# ESP_Grow_Rev_A.net
KiCad netlist of a schematic drawn in Altium Designer
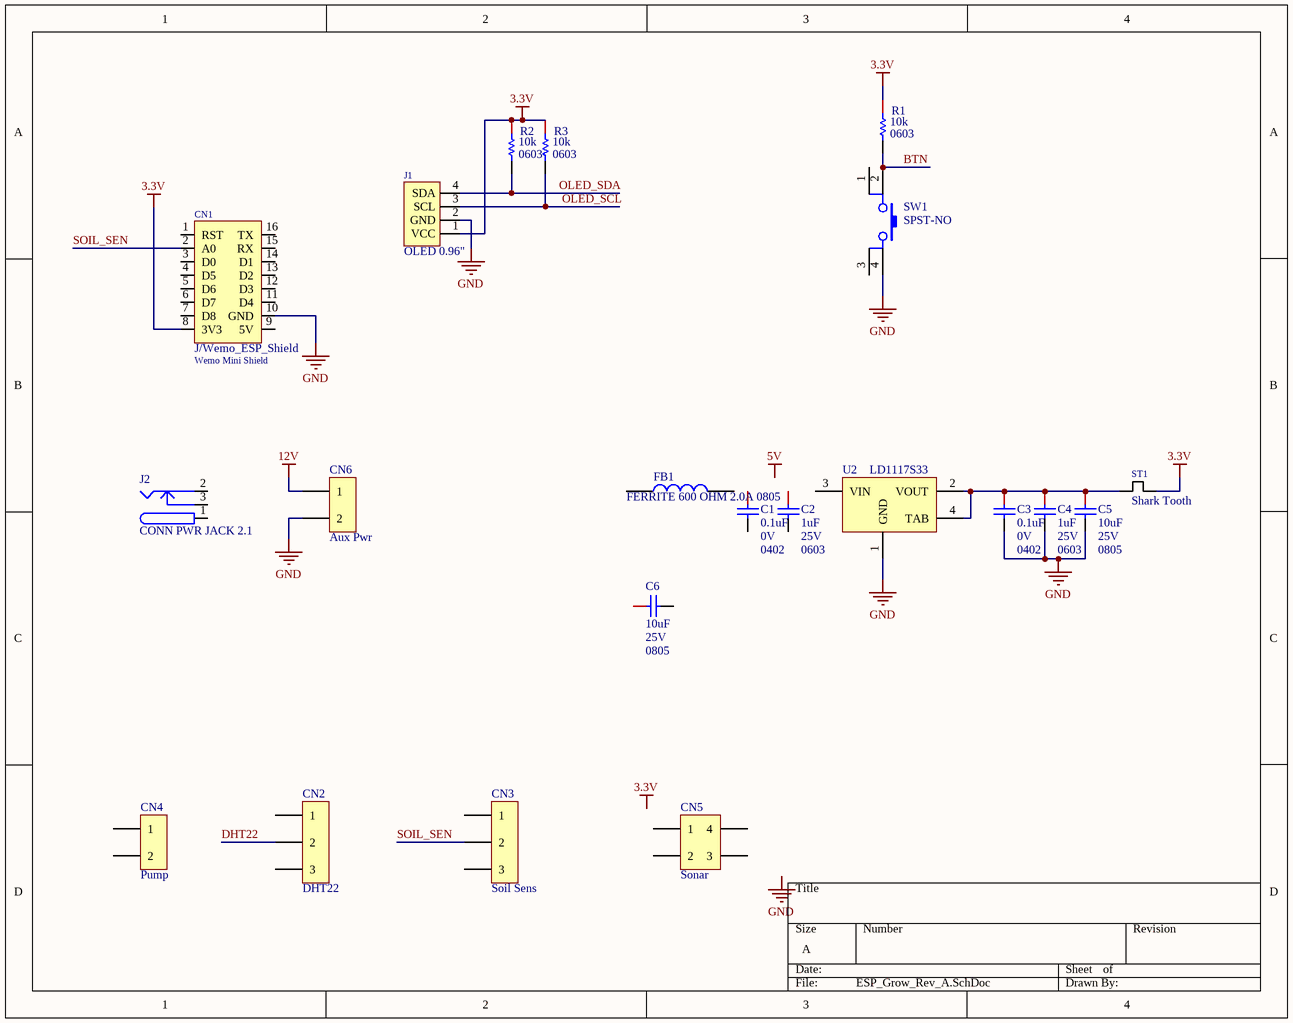
[diagram p0: ESP_Grow_Rev_A.SchDoc]

(export (version "E")
  (design (tool "Eeschema 10.0.6"))
  (components
    (comp (ref "C1")
      (value "0.1uF")
      (footprint "CAPC0402(1005)_M")
      (description "CAP CER 0.1UF 50V X7R 0402")
      (fields
        (field (name "VOLTAGE (RATED)") "0V")
        (field (name "PACKAGE (IMPERIAL)") "0402")
        (field (name "TOLERANCE") "20%")
      )
      (libsource (lib "OLogic Nexus Vault") (part "=Capacitance"))
    )
    (comp (ref "C2")
      (value "1uF")
      (footprint "CAPC0603(1608)_N")
      (description "CAP CER 1UF 25V 10% X7R 0603")
      (fields
        (field (name "VOLTAGE (RATED)") "25V")
        (field (name "PACKAGE (IMPERIAL)") "0603")
        (field (name "TOLERANCE") "10%")
      )
      (libsource (lib "OLogic Nexus Vault") (part "=Capacitance"))
    )
    (comp (ref "C3")
      (value "0.1uF")
      (footprint "CAPC0402(1005)_M")
      (description "CAP CER 0.1UF 50V X7R 0402")
      (fields
        (field (name "VOLTAGE (RATED)") "0V")
        (field (name "PACKAGE (IMPERIAL)") "0402")
        (field (name "TOLERANCE") "20%")
      )
      (libsource (lib "OLogic Nexus Vault") (part "=Capacitance"))
    )
    (comp (ref "C4")
      (value "1uF")
      (footprint "CAPC0603(1608)_N")
      (description "CAP CER 1UF 25V 10% X7R 0603")
      (fields
        (field (name "VOLTAGE (RATED)") "25V")
        (field (name "PACKAGE (IMPERIAL)") "0603")
        (field (name "TOLERANCE") "10%")
      )
      (libsource (lib "OLogic Nexus Vault") (part "=Capacitance"))
    )
    (comp (ref "C5")
      (value "10uF")
      (footprint "CAPC0805(2012)_L")
      (description "CAP CER 10UF 25V X6S 0805")
      (fields
        (field (name "VOLTAGE (RATED)") "25V")
        (field (name "PACKAGE (IMPERIAL)") "0805")
        (field (name "TOLERANCE") "20%")
      )
      (libsource (lib "OLogic Nexus Vault") (part "=Capacitance"))
    )
    (comp (ref "C6")
      (value "10uF")
      (footprint "CAPC0805(2012)_L")
      (description "CAP CER 10UF 25V X6S 0805")
      (fields
        (field (name "VOLTAGE (RATED)") "25V")
        (field (name "PACKAGE (IMPERIAL)") "0805")
        (field (name "TOLERANCE") "20%")
      )
      (libsource (lib "OLogic Nexus Vault") (part "=Capacitance"))
    )
    (comp (ref "CN1")
      (value "J/Wemo_ESP_Shield")
      (footprint "Wemos_d1")
      (description "Wemo Mini Shield for ESP-12")
      (fields (field (name "NAME") "Wemo Mini Shield"))
      (libsource (lib "Kyle_Lib_04-20-19") (part "J/Wemo_ESP_Shield"))
    )
    (comp (ref "CN2")
      (value "DHT22")
      (footprint "Molex 1x3 Microfit 90deg")
      (description "Molex Microfit 1x3 90deg Header")
      (fields
        (field (name "MANUFACTURER") "Molex Inc")
        (field (name "MANUFACTURER PART NUMBER") "0436500304")
      )
      (libsource (lib "ologic-library_2018-09-22") (part "CMP-001-0428-01"))
    )
    (comp (ref "CN3")
      (value "Soil Sens")
      (footprint "Molex 1x3 Microfit 90deg")
      (description "Molex Microfit 1x3 90deg Header")
      (fields
        (field (name "MANUFACTURER") "Molex Inc")
        (field (name "MANUFACTURER PART NUMBER") "0436500304")
      )
      (libsource (lib "ologic-library_2018-09-22") (part "CMP-001-0428-01"))
    )
    (comp (ref "CN4")
      (value "Pump")
      (footprint "Molex 1x2 Microfit 90deg")
      (description "Molex Microfit 1x2 90deg Header")
      (fields (field (name "MANUFACTURER") "Molex") (field (name "MANUFACTURER PART NUMBER") "43650-0204"))
      (libsource (lib "ologic-library_2018-09-22") (part "CMP-001-0425-01"))
    )
    (comp (ref "CN5")
      (value "Sonar")
      (footprint "Molex 2x2 Microfit 90deg")
      (description "Molex Microfit 2x2 90deg Header")
      (fields
        (field (name "MANUFACTURER") "Molex Inc")
        (field (name "MANUFACTURER PART NUMBER") "0430450400")
      )
      (libsource (lib "ologic-library_2018-09-22") (part "CMP-001-0429-01"))
    )
    (comp (ref "CN6")
      (value "Aux Pwr")
      (footprint "Molex 1x2 Microfit 3.0")
      (description "Molex Microfit 1x2 Vert Header")
      (fields
        (field (name "MANUFACTURER PART NUMBER") "0430450227")
        (field (name "MANUFACTURER") "Molex, LLC")
      )
      (libsource (lib "OLogic Nexus Vault") (part "MICROFIT 3.0 HDR VERT CPI 2CKT"))
    )
    (comp (ref "FB1")
      (value "FERRITE 600 OHM 2.0A 0805")
      (footprint "RESC0805(2012)_N")
      (description "600 OHM 0805 2.0A")
      (fields
        (field (name "MANUFACTURER PART NUMBER") "742792040")
        (field (name "MANUFACTURER") "Wurth Electronics Inc")
        (field (name "CREATOR") "osman")
      )
      (libsource (lib "OLogic Nexus Vault") (part "FERRITE 600 OHM 2.0A 0805"))
    )
    (comp (ref "J1")
      (value "OLED 0.96\"")
      (footprint "OLED_0.96_I2C")
      (description "SSD1306 I2C OLED 0.96\"")
      (libsource (lib "Kyle_Lib_04-20-19") (part "OLED_0.96_I2C"))
    )
    (comp (ref "J2")
      (value "CONN PWR JACK 2.1")
      (footprint "CONN_PWR_JACK_2.1x5.5mm")
      (description "2.1 mm barrel jack")
      (fields
        (field (name "MANUFACTURER PART NUMBER") "PJ-002A")
        (field (name "MANUFACTURER") "CUI Inc")
        (field (name "PUBLISHER") "Altium Limited")
      )
      (libsource (lib "OLogic Nexus Vault") (part "CONN PWR JACK 2.1"))
    )
    (comp (ref "R1")
      (value "10K")
      (footprint "RESC0603(1608)_M")
      (description "RES 10K OHM 1/10W 1% 0603 SMD")
      (fields
        (field (name "PACKAGE (IMPERIAL)") "0603")
        (field (name "RESISTANCE") "10k")
        (field (name "POWER") "100mW")
        (field (name "TOLERANCE") "1%")
      )
      (libsource (lib "OLogic Nexus Vault") (part "=Resistance"))
    )
    (comp (ref "R2")
      (value "10K")
      (footprint "RESC0603(1608)_M")
      (description "RES 10K OHM 1/10W 1% 0603 SMD")
      (fields
        (field (name "PACKAGE (IMPERIAL)") "0603")
        (field (name "RESISTANCE") "10k")
        (field (name "POWER") "100mW")
        (field (name "TOLERANCE") "1%")
      )
      (libsource (lib "OLogic Nexus Vault") (part "=Resistance"))
    )
    (comp (ref "R3")
      (value "10K")
      (footprint "RESC0603(1608)_M")
      (description "RES 10K OHM 1/10W 1% 0603 SMD")
      (fields
        (field (name "PACKAGE (IMPERIAL)") "0603")
        (field (name "RESISTANCE") "10k")
        (field (name "POWER") "100mW")
        (field (name "TOLERANCE") "1%")
      )
      (libsource (lib "OLogic Nexus Vault") (part "=Resistance"))
    )
    (comp (ref "ST1")
      (value "Shark Tooth")
      (footprint "SharkTooth")
      (description "Sharks Tooth Small")
      (libsource (lib "Kyle_Lib_04-20-19") (part "Shark Tooth"))
    )
    (comp (ref "SW1")
      (value "PTS645SM43SMTR92 LFS")
      (footprint "SW TACT Red 6mm x 6mm")
      (description "SWITCH TACTILE SPST-NO 0.05A 12V")
      (fields (field (name "CIRCUIT") "SPST-NO") (field (name "MANUFACTURER") "C&K"))
      (libsource (lib "OLogic Nexus Vault") (part "PTS645SM43SMTR92 LFS"))
    )
    (comp (ref "U2")
      (value "LD1117S33")
      (footprint "DSO-G3")
      (description "3.3 volt fixed regulator, 800mA")
      (libsource (lib "OLogic Nexus Vault") (part "LD1117S33"))
    )
  )
  (nets
    (net (code "1") (name "/BTN") (class "Default")
      (node (ref "R1") (pin "2") (pinfunction "2_2") (pintype "passive"))
      (node (ref "SW1") (pin "2") (pinfunction "2_2") (pintype "passive"))
    )
    (net (code "2") (name "/DHT22") (class "Default")
      (node (ref "CN2") (pin "2") (pinfunction "2_2") (pintype "passive"))
    )
    (net (code "3") (name "/OLED_SCL") (class "Default")
      (node (ref "J1") (pin "3") (pinfunction "SCL_3") (pintype "passive"))
      (node (ref "R3") (pin "2") (pinfunction "2_2") (pintype "passive"))
    )
    (net (code "4") (name "/OLED_SDA") (class "Default")
      (node (ref "J1") (pin "4") (pinfunction "SDA_4") (pintype "passive"))
      (node (ref "R2") (pin "2") (pinfunction "2_2") (pintype "passive"))
    )
    (net (code "5") (name "/SOIL_SEN") (class "Default")
      (node (ref "CN1") (pin "2") (pinfunction "A0_2") (pintype "power_in"))
      (node (ref "CN3") (pin "2") (pinfunction "2_2") (pintype "passive"))
    )
    (net (code "6") (name "3.3V") (class "Default")
      (node (ref "CN1") (pin "8") (pinfunction "3V3_8") (pintype "power_in"))
      (node (ref "J1") (pin "1") (pinfunction "VCC_1") (pintype "passive"))
      (node (ref "R1") (pin "1") (pinfunction "1_1") (pintype "passive"))
      (node (ref "R2") (pin "1") (pinfunction "1_1") (pintype "passive"))
      (node (ref "R3") (pin "1") (pinfunction "1_1") (pintype "passive"))
      (node (ref "ST1") (pin "2") (pinfunction "2_2") (pintype "power_in"))
    )
    (net (code "8") (name "12V") (class "Default")
      (node (ref "CN6") (pin "1") (pinfunction "1_1") (pintype "passive"))
    )
    (net (code "9") (name "GND") (class "Default")
      (node (ref "C3") (pin "2") (pinfunction "2_2") (pintype "passive"))
      (node (ref "C4") (pin "2") (pinfunction "2_2") (pintype "passive"))
      (node (ref "C5") (pin "2") (pinfunction "2_2") (pintype "passive"))
      (node (ref "CN1") (pin "10") (pinfunction "GND_10") (pintype "power_in"))
      (node (ref "CN6") (pin "2") (pinfunction "2_2") (pintype "passive"))
      (node (ref "J1") (pin "2") (pinfunction "GND_2") (pintype "passive"))
      (node (ref "SW1") (pin "4") (pinfunction "4_4") (pintype "passive"))
      (node (ref "U2") (pin "1") (pinfunction "GND_1") (pintype "power_in"))
    )
    (net (code "10") (name "Net-(U2-TAB)") (class "Default")
      (node (ref "C3") (pin "1") (pinfunction "1_1") (pintype "passive"))
      (node (ref "C4") (pin "1") (pinfunction "1_1") (pintype "passive"))
      (node (ref "C5") (pin "1") (pinfunction "1_1") (pintype "passive"))
      (node (ref "ST1") (pin "1") (pinfunction "1_1") (pintype "power_in"))
      (node (ref "U2") (pin "2") (pinfunction "VOUT_2") (pintype "power_in"))
      (node (ref "U2") (pin "4") (pinfunction "TAB_4") (pintype "power_in"))
    )
    (net (code "11") (name "unconnected-(C1-Pad1)") (class "Default")
      (node (ref "C1") (pin "1") (pinfunction "1_1") (pintype "passive"))
    )
    (net (code "12") (name "unconnected-(C1-Pad2)") (class "Default")
      (node (ref "C1") (pin "2") (pinfunction "2_2") (pintype "passive"))
    )
    (net (code "13") (name "unconnected-(C2-Pad1)") (class "Default")
      (node (ref "C2") (pin "1") (pinfunction "1_1") (pintype "passive"))
    )
    (net (code "14") (name "unconnected-(C2-Pad2)") (class "Default")
      (node (ref "C2") (pin "2") (pinfunction "2_2") (pintype "passive"))
    )
    (net (code "15") (name "unconnected-(C6-Pad1)") (class "Default")
      (node (ref "C6") (pin "1") (pinfunction "1_1") (pintype "passive"))
    )
    (net (code "16") (name "unconnected-(C6-Pad2)") (class "Default")
      (node (ref "C6") (pin "2") (pinfunction "2_2") (pintype "passive"))
    )
    (net (code "17") (name "unconnected-(CN1-5V-Pad9)") (class "Default")
      (node (ref "CN1") (pin "9") (pinfunction "5V_9") (pintype "power_in"))
    )
    (net (code "18") (name "unconnected-(CN1-D0-Pad3)") (class "Default")
      (node (ref "CN1") (pin "3") (pinfunction "D0_3") (pintype "power_in"))
    )
    (net (code "19") (name "unconnected-(CN1-D1-Pad14)") (class "Default")
      (node (ref "CN1") (pin "14") (pinfunction "D1_14") (pintype "power_in"))
    )
    (net (code "20") (name "unconnected-(CN1-D2-Pad13)") (class "Default")
      (node (ref "CN1") (pin "13") (pinfunction "D2_13") (pintype "power_in"))
    )
    (net (code "21") (name "unconnected-(CN1-D3-Pad12)") (class "Default")
      (node (ref "CN1") (pin "12") (pinfunction "D3_12") (pintype "power_in"))
    )
    (net (code "22") (name "unconnected-(CN1-D4-Pad11)") (class "Default")
      (node (ref "CN1") (pin "11") (pinfunction "D4_11") (pintype "power_in"))
    )
    (net (code "23") (name "unconnected-(CN1-D5-Pad4)") (class "Default")
      (node (ref "CN1") (pin "4") (pinfunction "D5_4") (pintype "power_in"))
    )
    (net (code "24") (name "unconnected-(CN1-D6-Pad5)") (class "Default")
      (node (ref "CN1") (pin "5") (pinfunction "D6_5") (pintype "power_in"))
    )
    (net (code "25") (name "unconnected-(CN1-D7-Pad6)") (class "Default")
      (node (ref "CN1") (pin "6") (pinfunction "D7_6") (pintype "power_in"))
    )
    (net (code "26") (name "unconnected-(CN1-D8-Pad7)") (class "Default")
      (node (ref "CN1") (pin "7") (pinfunction "D8_7") (pintype "power_in"))
    )
    (net (code "27") (name "unconnected-(CN1-RST-Pad1)") (class "Default")
      (node (ref "CN1") (pin "1") (pinfunction "RST_1") (pintype "power_in"))
    )
    (net (code "28") (name "unconnected-(CN1-RX-Pad15)") (class "Default")
      (node (ref "CN1") (pin "15") (pinfunction "RX_15") (pintype "power_in"))
    )
    (net (code "29") (name "unconnected-(CN1-TX-Pad16)") (class "Default")
      (node (ref "CN1") (pin "16") (pinfunction "TX_16") (pintype "power_in"))
    )
    (net (code "30") (name "unconnected-(CN2-Pad1)") (class "Default")
      (node (ref "CN2") (pin "1") (pinfunction "1_1") (pintype "passive"))
    )
    (net (code "31") (name "unconnected-(CN2-Pad3)") (class "Default")
      (node (ref "CN2") (pin "3") (pinfunction "3_3") (pintype "passive"))
    )
    (net (code "32") (name "unconnected-(CN3-Pad1)") (class "Default")
      (node (ref "CN3") (pin "1") (pinfunction "1_1") (pintype "passive"))
    )
    (net (code "33") (name "unconnected-(CN3-Pad3)") (class "Default")
      (node (ref "CN3") (pin "3") (pinfunction "3_3") (pintype "passive"))
    )
    (net (code "34") (name "unconnected-(CN4-Pad1)") (class "Default")
      (node (ref "CN4") (pin "1") (pinfunction "1_1") (pintype "passive"))
    )
    (net (code "35") (name "unconnected-(CN4-Pad2)") (class "Default")
      (node (ref "CN4") (pin "2") (pinfunction "2_2") (pintype "passive"))
    )
    (net (code "36") (name "unconnected-(CN5-Pad1)") (class "Default")
      (node (ref "CN5") (pin "1") (pinfunction "1_1") (pintype "passive"))
    )
    (net (code "37") (name "unconnected-(CN5-Pad2)") (class "Default")
      (node (ref "CN5") (pin "2") (pinfunction "2_2") (pintype "passive"))
    )
    (net (code "38") (name "unconnected-(CN5-Pad3)") (class "Default")
      (node (ref "CN5") (pin "3") (pinfunction "3_3") (pintype "passive"))
    )
    (net (code "39") (name "unconnected-(CN5-Pad4)") (class "Default")
      (node (ref "CN5") (pin "4") (pinfunction "4_4") (pintype "passive"))
    )
    (net (code "40") (name "unconnected-(FB1-Pad1)") (class "Default")
      (node (ref "FB1") (pin "1") (pinfunction "1_1") (pintype "passive"))
    )
    (net (code "41") (name "unconnected-(FB1-Pad2)") (class "Default")
      (node (ref "FB1") (pin "2") (pinfunction "2_2") (pintype "passive"))
    )
    (net (code "42") (name "unconnected-(J2-Pad1)") (class "Default")
      (node (ref "J2") (pin "1") (pinfunction "1_1") (pintype "power_in"))
    )
    (net (code "43") (name "unconnected-(J2-Pad2)") (class "Default")
      (node (ref "J2") (pin "2") (pinfunction "2_2") (pintype "power_in"))
    )
    (net (code "44") (name "unconnected-(J2-Pad3)") (class "Default")
      (node (ref "J2") (pin "3") (pinfunction "3_3") (pintype "power_in"))
    )
    (net (code "45") (name "unconnected-(SW1-Pad1)") (class "Default")
      (node (ref "SW1") (pin "1") (pinfunction "1_1") (pintype "passive"))
    )
    (net (code "46") (name "unconnected-(SW1-Pad3)") (class "Default")
      (node (ref "SW1") (pin "3") (pinfunction "3_3") (pintype "passive"))
    )
    (net (code "47") (name "unconnected-(U2-VIN-Pad3)") (class "Default")
      (node (ref "U2") (pin "3") (pinfunction "VIN_3") (pintype "power_in"))
    )
  )
)
